# PowerSupply.net
KiCad netlist of a schematic drawn in Altium Designer
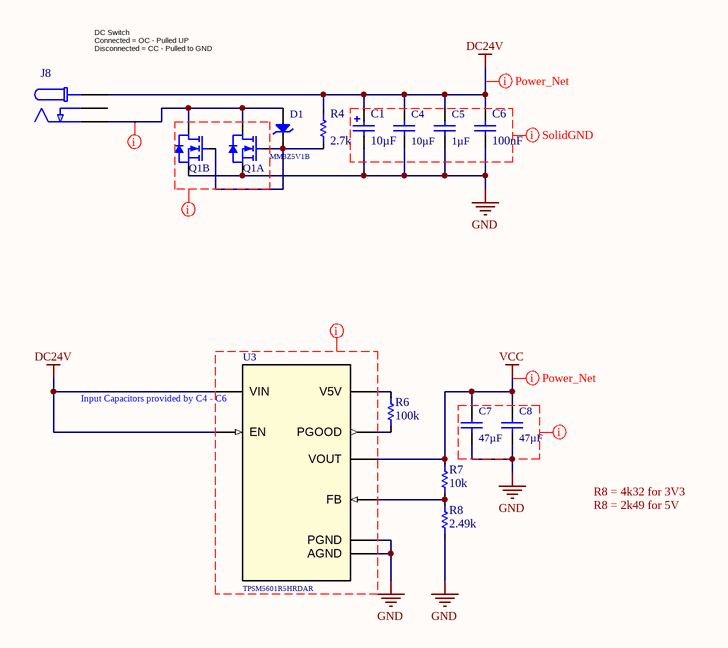
[diagram p0: PowerSupply.SchDoc]

(export (version "E")
  (design (tool "Eeschema 10.0.6"))
  (components
    (comp (ref "C1")
      (value "10µF")
      (footprint "CAP_EEEFK1H100P")
      (description "10µF ±20% 50V SMD Aluminum Electrolytic Capacitor Surface Mount D")
      (fields (field (name "VOLTAGE") "50V") (field (name "TOLERANCE") "20%"))
      (libsource (lib "Sainsbury Wellcome Centre") (part "Cap Pol"))
    )
    (comp (ref "C4")
      (value "10µF")
      (footprint "CAPC3225X279X50NL20T25")
      (description "10uF ±10% 50V Ceramic Capacitor X7R 1210 (3225 Metric)")
      (fields (field (name "TOLERANCE") "10%") (field (name "Comment") "C1210-10uF-50V-10%-X7R"))
      (libsource (lib "Sainsbury Wellcome Centre") (part "Cap"))
    )
    (comp (ref "C5")
      (value "1µF")
      (footprint "CAPC0805(2012)130_N")
      (description "1uF ±10% 50V Ceramic Capacitor X7R 0805 (2012 Metric)")
      (fields (field (name "TOLERANCE") "10%") (field (name "Comment") "C0805-1uF-50V-10%-X7R"))
      (libsource (lib "Sainsbury Wellcome Centre") (part "Cap"))
    )
    (comp (ref "C6")
      (value "100nF")
      (footprint "FP-GRM188-0_1-e0_2_0_5-IPC_B")
      (description "0.1µF ±10% 100V Ceramic Capacitor X7R 0603 (1608 Metric)")
      (fields (field (name "TOLERANCE") "10%") (field (name "VOLTAGE") "100V"))
      (libsource (lib "Sainsbury Wellcome Centre") (part "Cap"))
    )
    (comp (ref "C7")
      (value "47µF")
      (footprint "FP-GRM32E-0_3-0_2-IPC_B")
      (description "47uF ±10% 10V Ceramic Capacitor X7R 1210 (3225 Metric)")
      (fields (field (name "TOLERANCE") "10%") (field (name "VOLTAGE") "10V"))
      (libsource (lib "Sainsbury Wellcome Centre") (part "Cap"))
    )
    (comp (ref "C8")
      (value "47µF")
      (footprint "FP-GRM32E-0_3-0_2-IPC_B")
      (description "47uF ±10% 10V Ceramic Capacitor X7R 1210 (3225 Metric)")
      (fields (field (name "TOLERANCE") "10%") (field (name "VOLTAGE") "10V"))
      (libsource (lib "Sainsbury Wellcome Centre") (part "Cap"))
    )
    (comp (ref "D1")
      (value "MM3Z10VB")
      (footprint "SODFL250X100-2N")
      (description "DIODE ZENER 10V 200MW SOD323F")
      (fields (field (name "PARTNUMBER") "MM3Z5V1B") (field (name "TOLERANCE") "2%"))
      (libsource (lib "Sainsbury Wellcome Centre") (part "Zener-A1C2"))
    )
    (comp (ref "J8")
      (value "694108105102")
      (footprint "WE_694108105102")
      (description "DC Power Connectors WR-DC PwrJk CtrPnSMT Right Angled W/Peg")
      (libsource (lib "Sainsbury Wellcome Centre") (part "694108105102"))
    )
    (comp (ref "Q1")
      (value "FDMC8030")
      (footprint "TRANS_FDMC8030")
      (description "ON SEMICONDUCTOR - FDMC8030 - Dual MOSFET, Dual N Channel, 12 A, 40 V, 0.008 ohm, 10 V, 1.5 V")
      (libsource (lib "Sainsbury Wellcome Centre") (part "FDMC8030"))
    )
    (comp (ref "R4")
      (value "2.7k")
      (footprint "FP-CPF0603-IPC_B")
      (description "Surface Mount Resistor 2k7 Ohm 1/16 W 0.1% 0603 (1608 Metric)")
      (fields (field (name "TOLERANCE") "0.1%") (field (name "Comment") "R0603-2k7-1/16W-0.1%"))
      (libsource (lib "Sainsbury Wellcome Centre") (part "Res"))
    )
    (comp (ref "R6")
      (value "100k")
      (footprint "FP-CPF0603-IPC_B")
      (description "Surface Mount Resistor 100k Ohm 1/16 W 0.1% 0603 (1608 Metric)")
      (fields (field (name "TOLERANCE") "0.1%") (field (name "Comment") "R0603-100k-1/16W-0.1%"))
      (libsource (lib "Sainsbury Wellcome Centre") (part "Res"))
    )
    (comp (ref "R7")
      (value "10k")
      (footprint "FP-CPF0603-IPC_B")
      (description "Surface Mount Resistor 10k Ohm 1/16 W 0.1% 0603 (1608 Metric)")
      (fields (field (name "TOLERANCE") "0.1%") (field (name "Comment") "R0603-10k-1/16W-0.1%"))
      (libsource (lib "Sainsbury Wellcome Centre") (part "Res"))
    )
    (comp (ref "R8")
      (value "2.49k")
      (footprint "FP-CPF0603-IPC_B")
      (description "Surface Mount Resistor 2.49k Ohm 1/16 W 0.1% 0603 (1608 Metric)")
      (fields (field (name "TOLERANCE") "0.1%") (field (name "Comment") "R0603-2k49-1/16W-0.1%"))
      (libsource (lib "Sainsbury Wellcome Centre") (part "Res"))
    )
    (comp (ref "U3")
      (value "TPSM5601R5HRDAR")
      (footprint "IC_TPSM5601R5HRDAR")
      (libsource (lib "Sainsbury Wellcome Centre") (part "TPSM5601R5Hx"))
    )
  )
  (nets
    (net (code "1") (name "DC24V") (class "Default")
      (node (ref "C1") (pin "1") (pinfunction "1_1") (pintype "passive"))
      (node (ref "C4") (pin "2") (pinfunction "2_2") (pintype "passive"))
      (node (ref "C5") (pin "2") (pinfunction "2_2") (pintype "passive"))
      (node (ref "C6") (pin "2") (pinfunction "2_2") (pintype "passive"))
      (node (ref "J8") (pin "1") (pinfunction "1_1") (pintype "passive"))
      (node (ref "R4") (pin "2") (pinfunction "2_2") (pintype "passive"))
      (node (ref "U3") (pin "1") (pinfunction "VIN_1") (pintype "power_in"))
      (node (ref "U3") (pin "2") (pinfunction "EN_2") (pintype "input"))
    )
    (net (code "2") (name "GND") (class "Default")
      (node (ref "C1") (pin "2") (pinfunction "2_2") (pintype "passive"))
      (node (ref "C4") (pin "1") (pinfunction "1_1") (pintype "passive"))
      (node (ref "C5") (pin "1") (pinfunction "1_1") (pintype "passive"))
      (node (ref "C6") (pin "1") (pinfunction "1_1") (pintype "passive"))
      (node (ref "C7") (pin "1") (pinfunction "1_1") (pintype "passive"))
      (node (ref "C8") (pin "1") (pinfunction "1_1") (pintype "passive"))
      (node (ref "Q1") (pin "4") (pinfunction "S1_4") (pintype "passive"))
      (node (ref "Q1") (pin "5") (pinfunction "S2_5") (pintype "passive"))
      (node (ref "R8") (pin "1") (pinfunction "1_1") (pintype "passive"))
      (node (ref "U3") (pin "10") (pinfunction "AGND_10") (pintype "power_in"))
      (node (ref "U3") (pin "15") (pinfunction "PGND_15") (pintype "power_in"))
    )
    (net (code "3") (name "Net-(D1-A)") (class "Default")
      (node (ref "D1") (pin "1") (pinfunction "A_1") (pintype "passive"))
      (node (ref "J8") (pin "2") (pinfunction "2_2") (pintype "passive"))
      (node (ref "Q1") (pin "10") (pinfunction "D1_10") (pintype "passive"))
      (node (ref "Q1") (pin "9") (pinfunction "D2_9") (pintype "passive"))
    )
    (net (code "4") (name "Net-(D1-C)") (class "Default")
      (node (ref "D1") (pin "2") (pinfunction "C_2") (pintype "passive"))
      (node (ref "Q1") (pin "1") (pinfunction "G1_1") (pintype "passive"))
      (node (ref "Q1") (pin "8") (pinfunction "G2_8") (pintype "passive"))
      (node (ref "R4") (pin "1") (pinfunction "1_1") (pintype "passive"))
    )
    (net (code "5") (name "Net-(U3-FB)") (class "Default")
      (node (ref "R7") (pin "1") (pinfunction "1_1") (pintype "passive"))
      (node (ref "R8") (pin "2") (pinfunction "2_2") (pintype "passive"))
      (node (ref "U3") (pin "9") (pinfunction "FB_9") (pintype "input"))
    )
    (net (code "6") (name "Net-(U3-PGOOD)") (class "Default")
      (node (ref "R6") (pin "1") (pinfunction "1_1") (pintype "passive"))
      (node (ref "U3") (pin "12") (pinfunction "PGOOD_12") (pintype "output"))
    )
    (net (code "7") (name "Net-(U3-V5V)") (class "Default")
      (node (ref "R6") (pin "2") (pinfunction "2_2") (pintype "passive"))
      (node (ref "U3") (pin "11") (pinfunction "V5V_11") (pintype "power_in"))
    )
    (net (code "8") (name "VCC") (class "Default")
      (node (ref "C7") (pin "2") (pinfunction "2_2") (pintype "passive"))
      (node (ref "C8") (pin "2") (pinfunction "2_2") (pintype "passive"))
      (node (ref "R7") (pin "2") (pinfunction "2_2") (pintype "passive"))
      (node (ref "U3") (pin "7") (pinfunction "VOUT_7") (pintype "power_in"))
    )
    (net (code "9") (name "unconnected-(J8-Pad3)") (class "Default")
      (node (ref "J8") (pin "3") (pinfunction "3_3") (pintype "passive"))
    )
  )
)
